# Main.net
KiCad netlist of a schematic drawn in Altium Designer
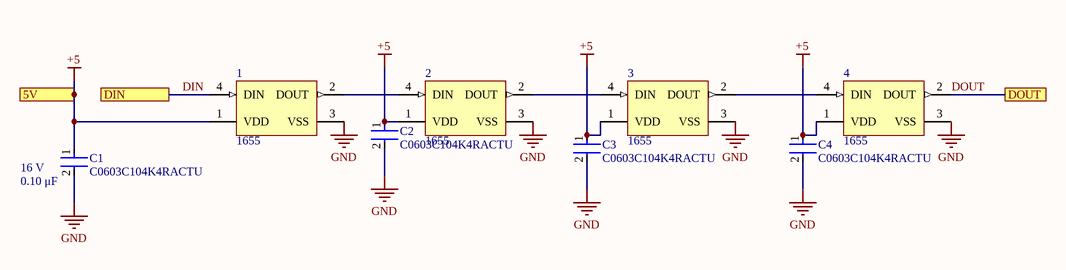
[diagram p0: Main.SchDoc]

(export (version "E")
  (design (tool "Eeschema 10.0.6"))
  (components
    (comp (ref "1")
      (value "1655")
      (footprint "ADA-RGB-1655_V")
      (fields (field (name "MANUFACTURER") "Adafruit-Industries-LLC"))
      (libsource (lib "Altium Content Vault") (part "ADA-RGB-1655-4"))
    )
    (comp (ref "2")
      (value "1655")
      (footprint "ADA-RGB-1655_V")
      (fields (field (name "MANUFACTURER") "Adafruit-Industries-LLC"))
      (libsource (lib "Altium Content Vault") (part "ADA-RGB-1655-4"))
    )
    (comp (ref "3")
      (value "1655")
      (footprint "ADA-RGB-1655_V")
      (fields (field (name "MANUFACTURER") "Adafruit-Industries-LLC"))
      (libsource (lib "Altium Content Vault") (part "ADA-RGB-1655-4"))
    )
    (comp (ref "4")
      (value "1655")
      (footprint "ADA-RGB-1655_V")
      (fields (field (name "MANUFACTURER") "Adafruit-Industries-LLC"))
      (libsource (lib "Altium Content Vault") (part "ADA-RGB-1655-4"))
    )
    (comp (ref "C1")
      (value "C0603C104K4RACTU")
      (footprint "FP-C0603C-CF-MFG")
      (description "Capacitor; Ceramic; Cap; .100uF; Tol 10%; SMT; Vol-Rtg 16V; X7R; Tape and Reel")
      (fields
        (field (name "ALTIUM_VALUE") "0.10 μF")
        (field (name "VOLTAGE RATING") "16 V")
        (field (name "OCTOPART") "https://octopart.com/c0603c104k4ractu-kemet-93067")
        (field (name "MANUFACTURER") "KEMET")
      )
      (libsource (lib "Altium Content Vault") (part "b4654b650e69147ec39a6b967a45e02"))
    )
    (comp (ref "C2")
      (value "C0603C104K4RACTU")
      (footprint "FP-C0603C-CF-MFG")
      (description "Capacitor; Ceramic; Cap; .100uF; Tol 10%; SMT; Vol-Rtg 16V; X7R; Tape and Reel")
      (fields
        (field (name "OCTOPART") "https://octopart.com/c0603c104k4ractu-kemet-93067")
        (field (name "MANUFACTURER") "KEMET")
      )
      (libsource (lib "Altium Content Vault") (part "b4654b650e69147ec39a6b967a45e02"))
    )
    (comp (ref "C3")
      (value "C0603C104K4RACTU")
      (footprint "FP-C0603C-CF-MFG")
      (description "Capacitor; Ceramic; Cap; .100uF; Tol 10%; SMT; Vol-Rtg 16V; X7R; Tape and Reel")
      (fields
        (field (name "OCTOPART") "https://octopart.com/c0603c104k4ractu-kemet-93067")
        (field (name "MANUFACTURER") "KEMET")
      )
      (libsource (lib "Altium Content Vault") (part "b4654b650e69147ec39a6b967a45e02"))
    )
    (comp (ref "C4")
      (value "C0603C104K4RACTU")
      (footprint "FP-C0603C-CF-MFG")
      (description "Capacitor; Ceramic; Cap; .100uF; Tol 10%; SMT; Vol-Rtg 16V; X7R; Tape and Reel")
      (fields
        (field (name "OCTOPART") "https://octopart.com/c0603c104k4ractu-kemet-93067")
        (field (name "MANUFACTURER") "KEMET")
      )
      (libsource (lib "Altium Content Vault") (part "b4654b650e69147ec39a6b967a45e02"))
    )
  )
  (nets
    (net (code "1") (name "+5") (class "Default")
      (node (ref "1") (pin "1") (pinfunction "VDD_1") (pintype "power_in"))
      (node (ref "2") (pin "1") (pinfunction "VDD_1") (pintype "power_in"))
      (node (ref "3") (pin "1") (pinfunction "VDD_1") (pintype "power_in"))
      (node (ref "4") (pin "1") (pinfunction "VDD_1") (pintype "power_in"))
      (node (ref "C1") (pin "1") (pinfunction "1_1") (pintype "passive"))
      (node (ref "C2") (pin "1") (pinfunction "1_1") (pintype "passive"))
      (node (ref "C3") (pin "1") (pinfunction "1_1") (pintype "passive"))
      (node (ref "C4") (pin "1") (pinfunction "1_1") (pintype "passive"))
    )
    (net (code "2") (name "/DIN") (class "Default")
      (node (ref "1") (pin "4") (pinfunction "DIN_4") (pintype "input"))
    )
    (net (code "3") (name "/DOUT") (class "Default")
      (node (ref "4") (pin "2") (pinfunction "DOUT_2") (pintype "output"))
    )
    (net (code "4") (name "GND") (class "Default")
      (node (ref "1") (pin "3") (pinfunction "VSS_3") (pintype "power_in"))
      (node (ref "2") (pin "3") (pinfunction "VSS_3") (pintype "power_in"))
      (node (ref "3") (pin "3") (pinfunction "VSS_3") (pintype "power_in"))
      (node (ref "4") (pin "3") (pinfunction "VSS_3") (pintype "power_in"))
      (node (ref "C1") (pin "2") (pinfunction "2_2") (pintype "passive"))
      (node (ref "C2") (pin "2") (pinfunction "2_2") (pintype "passive"))
      (node (ref "C3") (pin "2") (pinfunction "2_2") (pintype "passive"))
      (node (ref "C4") (pin "2") (pinfunction "2_2") (pintype "passive"))
    )
    (net (code "5") (name "Net-(1-DOUT)") (class "Default")
      (node (ref "1") (pin "2") (pinfunction "DOUT_2") (pintype "output"))
      (node (ref "2") (pin "4") (pinfunction "DIN_4") (pintype "input"))
    )
    (net (code "6") (name "Net-(2-DOUT)") (class "Default")
      (node (ref "2") (pin "2") (pinfunction "DOUT_2") (pintype "output"))
      (node (ref "3") (pin "4") (pinfunction "DIN_4") (pintype "input"))
    )
    (net (code "7") (name "Net-(3-DOUT)") (class "Default")
      (node (ref "3") (pin "2") (pinfunction "DOUT_2") (pintype "output"))
      (node (ref "4") (pin "4") (pinfunction "DIN_4") (pintype "input"))
    )
  )
)
